# Power.net
KiCad netlist of a schematic drawn in Altium Designer
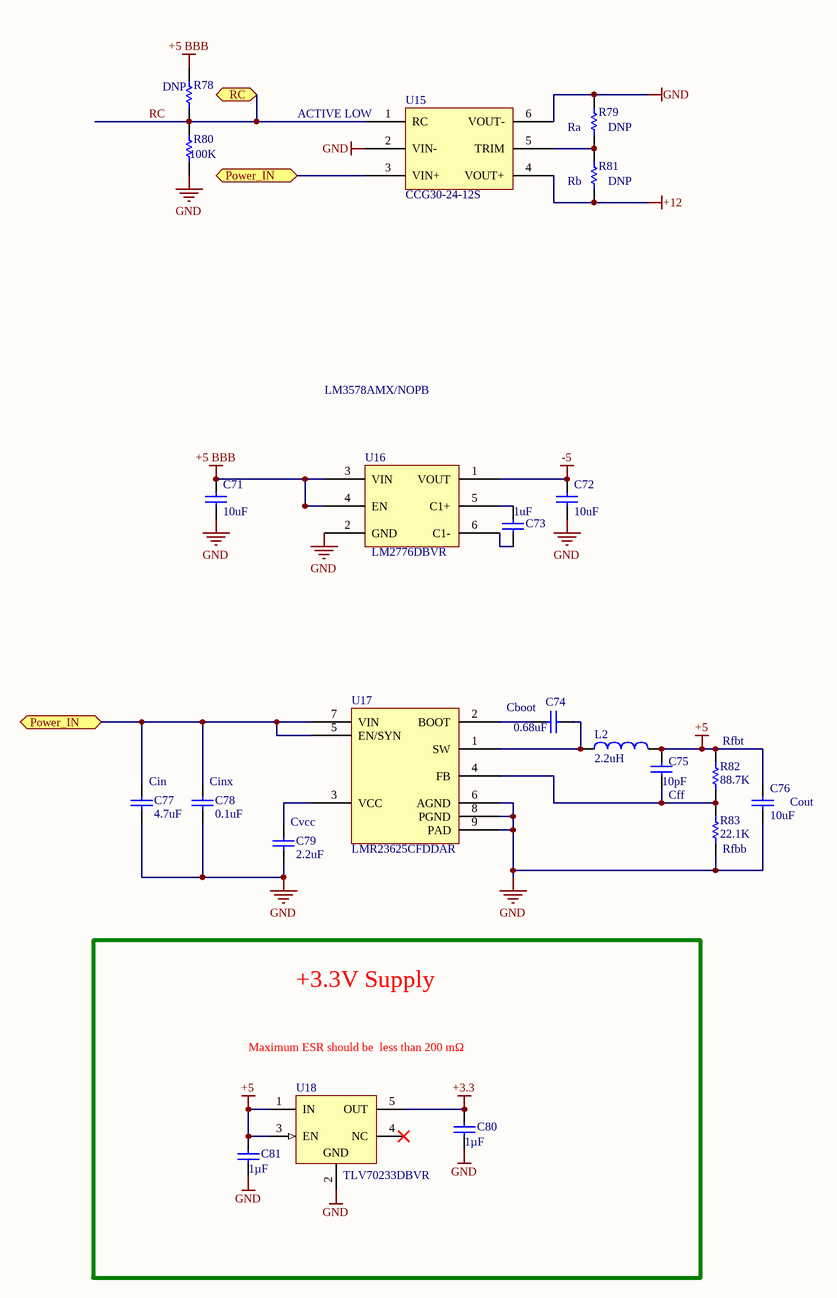
[diagram p0: Power.SchDoc]

(export (version "E")
  (design (tool "Eeschema 10.0.6"))
  (components
    (comp (ref "C71")
      (value "10uF")
      (footprint "CAPC0805(2012)145_N")
      (description "CAP CER 10UF 16V X6S 0805")
      (fields
        (field (name "MANUFACTURER") "TDK Corporation")
        (field (name "MANUFACTURER PART NUMBER") "C2012X6S1C106K085AC")
      )
      (libsource (lib "Altium Content Vault") (part "CMP-1036-04795-1"))
    )
    (comp (ref "C72")
      (value "10uF")
      (footprint "CAPC0805(2012)145_N")
      (description "CAP CER 10UF 16V X6S 0805")
      (fields
        (field (name "MANUFACTURER") "TDK Corporation")
        (field (name "MANUFACTURER PART NUMBER") "C2012X6S1C106K085AC")
      )
      (libsource (lib "Altium Content Vault") (part "CMP-1036-04795-1"))
    )
    (comp (ref "C73")
      (value "1uF")
      (footprint "CAPC0805(2012)145_N")
      (description "CAP CER 1UF 25V X7R 0805")
      (fields
        (field (name "MANUFACTURER") "Yageo")
        (field (name "MANUFACTURER PART NUMBER") "CC0805KKX7R6BB105")
      )
      (libsource (lib "Altium Content Vault") (part "CMP-1036-04795-1"))
    )
    (comp (ref "C74")
      (value "0.68uF")
      (footprint "1608[0603]")
      (description "CAP CER 0.68UF 50V X5R 0603")
      (fields
        (field (name "MANUFACTURER") "TDK Corporation")
        (field (name "MANUFACTURER PART NUMBER") "C1608X5R1H684K080AB")
      )
      (libsource (lib "Miscellaneous Devices") (part "Cap Semi"))
    )
    (comp (ref "C75")
      (value "10pF")
      (footprint "CAPC0805(2012)145_N")
      (description "CAP CER 10PF 16V C0G/NP0 0805")
      (fields
        (field (name "MANUFACTURER") "KEMET")
        (field (name "MANUFACTURER PART NUMBER") "C0805C100M4GACTU")
      )
      (libsource (lib "Altium Content Vault") (part "CMP-1036-04795-1"))
    )
    (comp (ref "C76")
      (value "10uF")
      (footprint "CAPC0805(2012)145_N")
      (description "CAP CER 10UF 16V X6S 0805")
      (fields
        (field (name "MANUFACTURER") "TDK Corporation")
        (field (name "MANUFACTURER PART NUMBER") "C2012X6S1C106K085AC")
      )
      (libsource (lib "Altium Content Vault") (part "CMP-1036-04795-1"))
    )
    (comp (ref "C77")
      (value "4.7uF")
      (footprint "C1210")
      (description "CAP CER 4.7UF 50V X7R 1210")
      (fields
        (field (name "MANUFACTURER") "Murata Electronics North America")
        (field (name "MANUFACTURER PART NUMBER") "GRM32ER71H475KA88L")
        (field (name "PUBLISHER") "Altium Limited")
      )
      (libsource (lib "Miscellaneous Devices") (part "Cap Semi"))
    )
    (comp (ref "C78")
      (value "0.1uF")
      (footprint "1608[0603]")
      (description "CAP CER 0.1UF 50V X5R 0603")
      (fields
        (field (name "MANUFACTURER") "TDK Corporation")
        (field (name "MANUFACTURER PART NUMBER") "C1608X5R1H104K080AA")
      )
      (libsource (lib "Miscellaneous Devices") (part "Cap Semi"))
    )
    (comp (ref "C79")
      (value "2.2uF")
      (footprint "1608[0603]")
      (description "CAP CER 2.2UF 10V X7R 0603")
      (libsource (lib "Miscellaneous Devices") (part "Cap Semi"))
    )
    (comp (ref "C80")
      (value "CAP CER 1UF 50V X7R 1210")
      (footprint "CAPC1206(3216)130_N")
      (fields
        (field (name "MANUFACTURER") "Murata Electronics North America")
        (field (name "MANUFACTURER PART NUMBER") "GRM32RR71H105KA01L")
        (field (name "CAPACITANCE") "1µF")
        (field (name "TOLERANCE") "±10%")
      )
      (libsource (lib "Altium Content Vault") (part "CMP-1037-04913-1"))
    )
    (comp (ref "C81")
      (value "CAP CER 1UF 50V X7R 1210")
      (footprint "CAPC1206(3216)130_N")
      (fields
        (field (name "MANUFACTURER") "Murata Electronics North America")
        (field (name "MANUFACTURER PART NUMBER") "GRM32RR71H105KA01L")
        (field (name "CAPACITANCE") "1µF")
        (field (name "TOLERANCE") "±10%")
      )
      (libsource (lib "Altium Content Vault") (part "CMP-1037-04913-1"))
    )
    (comp (ref "L2")
      (value "2.2uH")
      (footprint "PA4332")
      (description "FIXED IND 2.2UH 4.3A 48 MOHM SMD")
      (fields
        (field (name "MANUFACTURER") "Pulse Electronics Power")
        (field (name "MANUFACTURER PART NUMBER") "PA4332.222NLT")
      )
      (libsource (lib "Miscellaneous Devices") (part "Inductor"))
    )
    (comp (ref "R78")
      (value "DNP")
      (footprint "RESC0805(2012)_M")
      (description "RES SMD 100K OHM 1% 1/8W 0805")
      (fields
        (field (name "MANUFACTURER") "Vishay")
        (field (name "MANUFACTURER PART NUMBER") "CRCW0805100KFKEA")
      )
      (libsource (lib "Altium Content Vault") (part "CMP-1013-00017-1"))
    )
    (comp (ref "R79")
      (value "DNP")
      (footprint "RESC0805(2012)_M")
      (description "Vout = 12.05 ­ (445.7 / 63.1+Ra)")
      (libsource (lib "Altium Content Vault") (part "CMP-1013-00017-1"))
    )
    (comp (ref "R80")
      (value "RES SMD 100K OHM 1% 1/8W 0805")
      (footprint "RESC0805(2012)_M")
      (fields
        (field (name "MANUFACTURER") "Vishay")
        (field (name "MANUFACTURER PART NUMBER") "CRCW0805100KFKEA")
        (field (name "TOLERANCE") "1%")
        (field (name "RESISTANCE") "100K")
      )
      (libsource (lib "Altium Content Vault") (part "CMP-1013-00017-1"))
    )
    (comp (ref "R81")
      (value "DNP")
      (footprint "RESC0805(2012)_M")
      (description "Vout = 12.05 + (50.96 / 22+Rb)")
      (libsource (lib "Altium Content Vault") (part "CMP-1013-00017-1"))
    )
    (comp (ref "R82")
      (value "88.7K")
      (footprint "RESC0805(2012)_M")
      (description "RES SMD 88.7K OHM 1% 1/8W 0805")
      (fields
        (field (name "MANUFACTURER") "Vishay Dale")
        (field (name "MANUFACTURER PART NUMBER") "CRCW080588K7FKEA")
      )
      (libsource (lib "Altium Content Vault") (part "CMP-1013-00017-1"))
    )
    (comp (ref "R83")
      (value "22.1K")
      (footprint "RESC0805(2012)_M")
      (description "RES SMD 22.1K OHM 1% 1/8W 0805")
      (fields
        (field (name "MANUFACTURER") "Vishay Dale")
        (field (name "MANUFACTURER PART NUMBER") "CRCW080522K1FKEA")
      )
      (libsource (lib "Altium Content Vault") (part "CMP-1013-00017-1"))
    )
    (comp (ref "U15")
      (value "CCG30-24-12S")
      (footprint "PXB15-24WD05/N")
      (description "DC DC CONVERTER 12V 30W")
      (fields
        (field (name "MANUFACTURER") "TDK-Lambda Americas Inc.")
        (field (name "MANUFACTURER PART NUMBER") "CCG302412S")
      )
      (libsource (lib "ZLS_Schematic_lib") (part "CCG302412S"))
    )
    (comp (ref "U16")
      (value "LM2776DBVR")
      (footprint "LM2776DBVR")
      (description "IC REG SWTCHD CAP INV 6SOT23")
      (fields (field (name "MANUFACTURER") "Texas Instruments"))
      (libsource (lib "ZLS_Schematic_lib") (part "LM2776DBVR"))
    )
    (comp (ref "U17")
      (value "LMR23625CFDDAR")
      (footprint "LMR23625CDDAR")
      (description "IC REG BUCK ADJ 2.5A SYNC 8SOPWR")
      (fields (field (name "MANUFACTURER") "Texas Instruments"))
      (libsource (lib "ZLS_Schematic_lib") (part "LMR23625CDDAR"))
    )
    (comp (ref "U18")
      (value "TLV70233DBVR")
      (footprint "DBV0005A_N")
      (fields (field (name "MANUFACTURER") "Texas Instruments") (field (name "BASE PART NUMBER") "TLV70233"))
      (libsource (lib "Altium Content Vault") (part "CMP-0394-00528-2"))
    )
  )
  (nets
    (net (code "1") (name "+3.3") (class "Default")
      (node (ref "C80") (pin "2") (pinfunction "2_2") (pintype "passive"))
      (node (ref "U18") (pin "5") (pinfunction "OUT_5") (pintype "power_in"))
    )
    (net (code "2") (name "+5") (class "Default")
      (node (ref "C75") (pin "1") (pinfunction "1_1") (pintype "passive"))
      (node (ref "C76") (pin "1") (pinfunction "1_1") (pintype "passive"))
      (node (ref "C81") (pin "2") (pinfunction "2_2") (pintype "passive"))
      (node (ref "L2") (pin "2") (pinfunction "2_2") (pintype "passive"))
      (node (ref "R82") (pin "2") (pinfunction "2_2") (pintype "passive"))
      (node (ref "U18") (pin "1") (pinfunction "IN_1") (pintype "power_in"))
      (node (ref "U18") (pin "3") (pinfunction "EN_3") (pintype "input"))
    )
    (net (code "3") (name "+5 BBB") (class "Default")
      (node (ref "C71") (pin "1") (pinfunction "1_1") (pintype "passive"))
      (node (ref "R78") (pin "1") (pinfunction "1_1") (pintype "passive"))
      (node (ref "U16") (pin "3") (pinfunction "VIN_3") (pintype "passive"))
      (node (ref "U16") (pin "4") (pinfunction "EN_4") (pintype "passive"))
    )
    (net (code "4") (name "+12") (class "Default")
      (node (ref "R81") (pin "1") (pinfunction "1_1") (pintype "passive"))
      (node (ref "U15") (pin "4") (pinfunction "VOUT+_4") (pintype "passive"))
    )
    (net (code "5") (name "-5") (class "Default")
      (node (ref "C72") (pin "1") (pinfunction "1_1") (pintype "passive"))
      (node (ref "U16") (pin "1") (pinfunction "VOUT_1") (pintype "passive"))
    )
    (net (code "6") (name "/Power_IN") (class "Default")
      (node (ref "C77") (pin "2") (pinfunction "2_2") (pintype "passive"))
      (node (ref "C78") (pin "2") (pinfunction "2_2") (pintype "passive"))
      (node (ref "U15") (pin "3") (pinfunction "VIN+_3") (pintype "passive"))
      (node (ref "U17") (pin "5") (pinfunction "EN/SYN_5") (pintype "passive"))
      (node (ref "U17") (pin "7") (pinfunction "VIN_7") (pintype "passive"))
    )
    (net (code "7") (name "/RC") (class "Default")
      (node (ref "R78") (pin "2") (pinfunction "2_2") (pintype "passive"))
      (node (ref "R80") (pin "1") (pinfunction "1_1") (pintype "passive"))
      (node (ref "U15") (pin "1") (pinfunction "RC_1") (pintype "passive"))
    )
    (net (code "8") (name "GND") (class "Default")
      (node (ref "C71") (pin "2") (pinfunction "2_2") (pintype "passive"))
      (node (ref "C72") (pin "2") (pinfunction "2_2") (pintype "passive"))
      (node (ref "C76") (pin "2") (pinfunction "2_2") (pintype "passive"))
      (node (ref "C77") (pin "1") (pinfunction "1_1") (pintype "passive"))
      (node (ref "C78") (pin "1") (pinfunction "1_1") (pintype "passive"))
      (node (ref "C79") (pin "1") (pinfunction "1_1") (pintype "passive"))
      (node (ref "C80") (pin "1") (pinfunction "1_1") (pintype "passive"))
      (node (ref "C81") (pin "1") (pinfunction "1_1") (pintype "passive"))
      (node (ref "R79") (pin "2") (pinfunction "2_2") (pintype "passive"))
      (node (ref "R80") (pin "2") (pinfunction "2_2") (pintype "passive"))
      (node (ref "R83") (pin "1") (pinfunction "1_1") (pintype "passive"))
      (node (ref "U15") (pin "2") (pinfunction "VIN-_2") (pintype "passive"))
      (node (ref "U15") (pin "6") (pinfunction "VOUT-_6") (pintype "passive"))
      (node (ref "U16") (pin "2") (pinfunction "GND_2") (pintype "passive"))
      (node (ref "U17") (pin "6") (pinfunction "AGND_6") (pintype "passive"))
      (node (ref "U17") (pin "8") (pinfunction "PGND_8") (pintype "passive"))
      (node (ref "U17") (pin "9") (pinfunction "PAD_9") (pintype "passive"))
      (node (ref "U18") (pin "2") (pinfunction "GND_2") (pintype "power_in"))
    )
    (net (code "9") (name "Net-(U15-TRIM)") (class "Default")
      (node (ref "R79") (pin "1") (pinfunction "1_1") (pintype "passive"))
      (node (ref "R81") (pin "2") (pinfunction "2_2") (pintype "passive"))
      (node (ref "U15") (pin "5") (pinfunction "TRIM_5") (pintype "passive"))
    )
    (net (code "10") (name "Net-(U16-C1+)") (class "Default")
      (node (ref "C73") (pin "1") (pinfunction "1_1") (pintype "passive"))
      (node (ref "U16") (pin "5") (pinfunction "C1+_5") (pintype "passive"))
    )
    (net (code "11") (name "Net-(U16-C1-)") (class "Default")
      (node (ref "C73") (pin "2") (pinfunction "2_2") (pintype "passive"))
      (node (ref "U16") (pin "6") (pinfunction "C1-_6") (pintype "passive"))
    )
    (net (code "12") (name "Net-(U17-BOOT)") (class "Default")
      (node (ref "C74") (pin "1") (pinfunction "1_1") (pintype "passive"))
      (node (ref "U17") (pin "2") (pinfunction "BOOT_2") (pintype "passive"))
    )
    (net (code "13") (name "Net-(U17-FB)") (class "Default")
      (node (ref "C75") (pin "2") (pinfunction "2_2") (pintype "passive"))
      (node (ref "R82") (pin "1") (pinfunction "1_1") (pintype "passive"))
      (node (ref "R83") (pin "2") (pinfunction "2_2") (pintype "passive"))
      (node (ref "U17") (pin "4") (pinfunction "FB_4") (pintype "passive"))
    )
    (net (code "14") (name "Net-(U17-SW)") (class "Default")
      (node (ref "C74") (pin "2") (pinfunction "2_2") (pintype "passive"))
      (node (ref "L2") (pin "1") (pinfunction "1_1") (pintype "passive"))
      (node (ref "U17") (pin "1") (pinfunction "SW_1") (pintype "passive"))
    )
    (net (code "15") (name "Net-(U17-VCC)") (class "Default")
      (node (ref "C79") (pin "2") (pinfunction "2_2") (pintype "passive"))
      (node (ref "U17") (pin "3") (pinfunction "VCC_3") (pintype "passive"))
    )
    (net (code "16") (name "unconnected-(U18-NC-Pad4)") (class "Default")
      (node (ref "U18") (pin "4") (pinfunction "NC_4") (pintype "passive+no_connect"))
    )
  )
)
